# iotssb.net
KiCad netlist of a schematic drawn in EAGLE
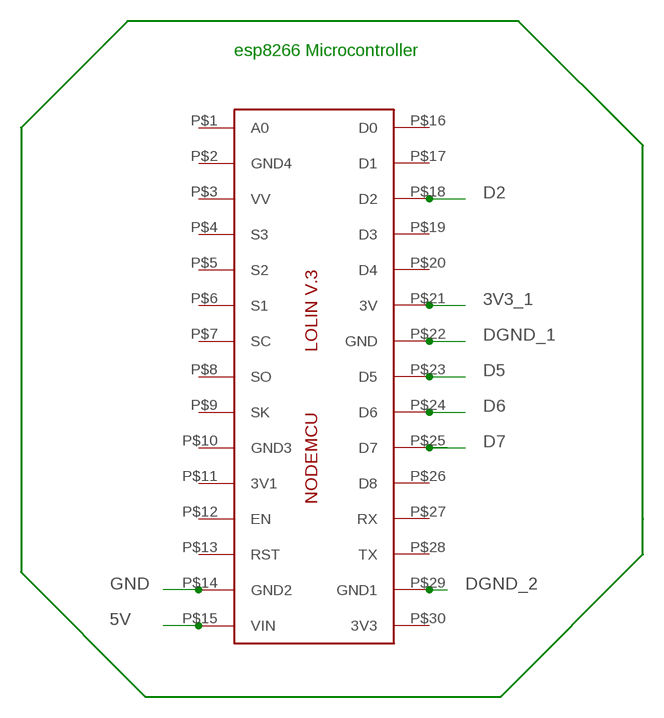
[diagram p0: schematic, sheet 1]
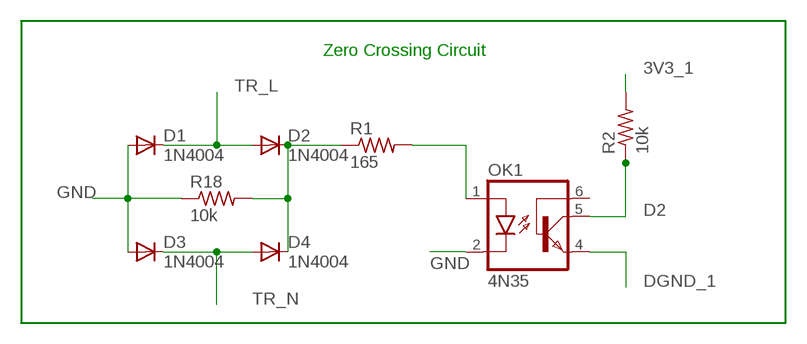
[diagram p1: schematic, sheet 2]
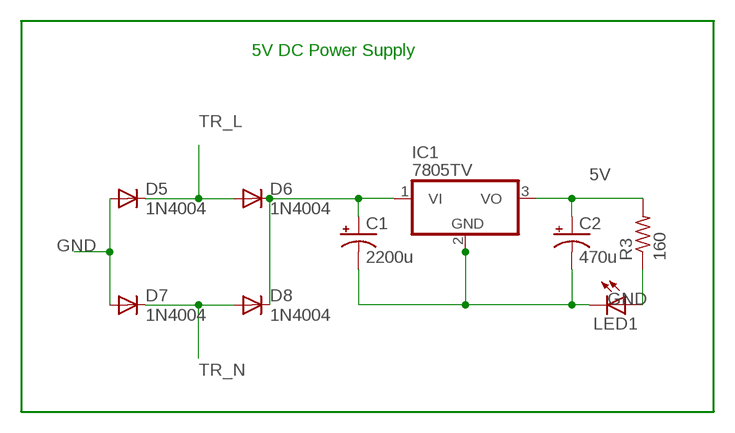
[diagram p2: schematic, sheet 3]
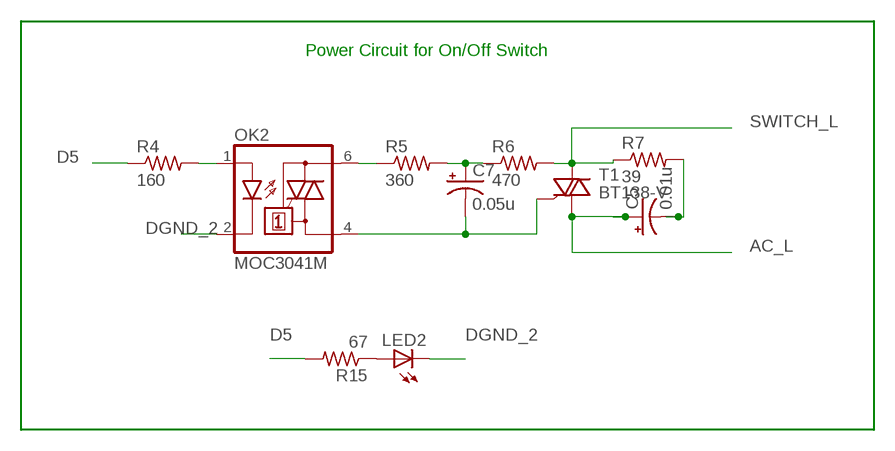
[diagram p3: schematic, sheet 4]
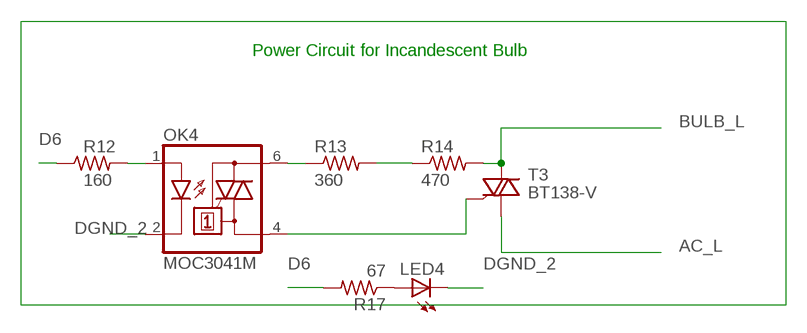
[diagram p4: schematic, sheet 5]
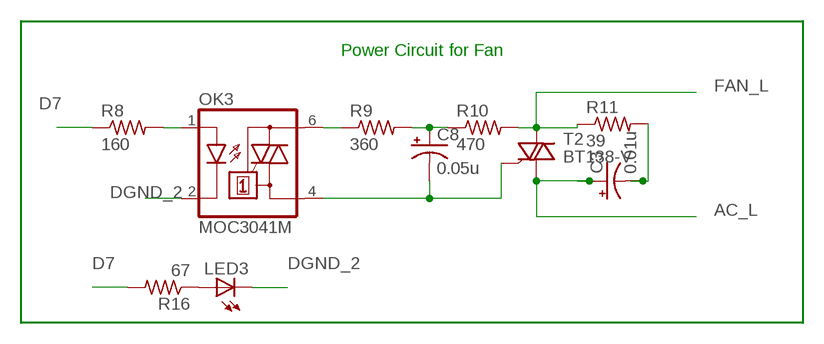
[diagram p5: schematic, sheet 6]
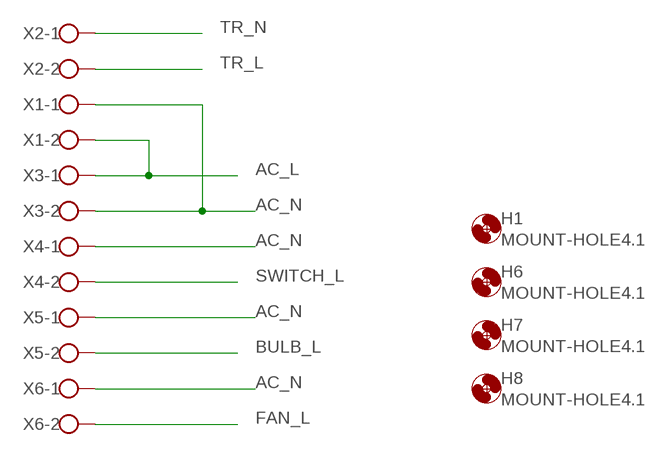
[diagram p6: schematic, sheet 7]

(export (version "E")
  (design (tool "Eeschema 10.0.6"))
  (components
    (comp (ref "C1")
      (value "2200u")
      (footprint "eagle-import:E7,5-18")
      (libsource (lib "eagle-import") (part "CPOL-USE7.5-18"))
    )
    (comp (ref "C2")
      (value "470u")
      (footprint "eagle-import:E5-13")
      (libsource (lib "eagle-import") (part "rcl_334_CPOL-USE5-13"))
    )
    (comp (ref "D5")
      (value "1N4004")
      (footprint "eagle-import:DO41-10")
      (libsource (lib "eagle-import") (part "1N4004"))
    )
    (comp (ref "D6")
      (value "1N4004")
      (footprint "eagle-import:DO41-10")
      (libsource (lib "eagle-import") (part "1N4004"))
    )
    (comp (ref "D7")
      (value "1N4004")
      (footprint "eagle-import:DO41-10")
      (libsource (lib "eagle-import") (part "1N4004"))
    )
    (comp (ref "D8")
      (value "1N4004")
      (footprint "eagle-import:DO41-10")
      (libsource (lib "eagle-import") (part "1N4004"))
    )
    (comp (ref "IC1")
      (value "7805TV")
      (footprint "eagle-import:TO220V")
      (libsource (lib "eagle-import") (part "78TV05"))
    )
    (comp (ref "LED1")
      (value "LED3MM")
      (footprint "eagle-import:LED3MM")
      (libsource (lib "eagle-import") (part "LED3MM"))
    )
    (comp (ref "R3")
      (value "160")
      (footprint "eagle-import:0207_10")
      (libsource (lib "eagle-import") (part "R-US_0207/10"))
    )
    (comp (ref "C5")
      (value "0.01u")
      (footprint "eagle-import:E5-13")
      (libsource (lib "eagle-import") (part "rcl_334_CPOL-USE5-13"))
    )
    (comp (ref "C7")
      (value "0.05u")
      (footprint "eagle-import:E5-13")
      (libsource (lib "eagle-import") (part "rcl_334_CPOL-USE5-13"))
    )
    (comp (ref "LED2")
      (value "LED3MM")
      (footprint "eagle-import:LED3MM")
      (libsource (lib "eagle-import") (part "LED3MM"))
    )
    (comp (ref "OK2")
      (value "MOC3041M")
      (footprint "eagle-import:DIL06")
      (fields (field (name "MF") "FAIRCHILD SEMICONDUCTOR"))
      (libsource (lib "eagle-import") (part "MOC3041M"))
    )
    (comp (ref "R4")
      (value "160")
      (footprint "eagle-import:0207_10")
      (libsource (lib "eagle-import") (part "R-US_0207/10"))
    )
    (comp (ref "R5")
      (value "360")
      (footprint "eagle-import:0207_15")
      (libsource (lib "eagle-import") (part "R-US_0207/15"))
    )
    (comp (ref "R6")
      (value "470")
      (footprint "eagle-import:0207_15")
      (libsource (lib "eagle-import") (part "R-US_0207/15"))
    )
    (comp (ref "R7")
      (value "39")
      (footprint "eagle-import:0207_15")
      (libsource (lib "eagle-import") (part "R-US_0207/15"))
    )
    (comp (ref "R15")
      (value "67")
      (footprint "eagle-import:0207_10")
      (libsource (lib "eagle-import") (part "R-US_0207/10"))
    )
    (comp (ref "T1")
      (value "BT138-V")
      (footprint "eagle-import:TO220BV")
      (libsource (lib "eagle-import") (part "BT138-V"))
    )
    (comp (ref "LED4")
      (value "LED3MM")
      (footprint "eagle-import:LED3MM")
      (libsource (lib "eagle-import") (part "LED3MM"))
    )
    (comp (ref "OK4")
      (value "MOC3041M")
      (footprint "eagle-import:DIL06")
      (fields (field (name "MF") "FAIRCHILD SEMICONDUCTOR"))
      (libsource (lib "eagle-import") (part "MOC3041M"))
    )
    (comp (ref "R12")
      (value "160")
      (footprint "eagle-import:0207_10")
      (libsource (lib "eagle-import") (part "R-US_0207/10"))
    )
    (comp (ref "R13")
      (value "360")
      (footprint "eagle-import:0207_15")
      (libsource (lib "eagle-import") (part "R-US_0207/15"))
    )
    (comp (ref "R14")
      (value "470")
      (footprint "eagle-import:0207_15")
      (libsource (lib "eagle-import") (part "R-US_0207/15"))
    )
    (comp (ref "R17")
      (value "67")
      (footprint "eagle-import:0207_10")
      (libsource (lib "eagle-import") (part "R-US_0207/10"))
    )
    (comp (ref "T3")
      (value "BT138-V")
      (footprint "eagle-import:TO220BV")
      (libsource (lib "eagle-import") (part "BT138-V"))
    )
    (comp (ref "C3")
      (value "0.01u")
      (footprint "eagle-import:E5-13")
      (libsource (lib "eagle-import") (part "rcl_334_CPOL-USE5-13"))
    )
    (comp (ref "C8")
      (value "0.05u")
      (footprint "eagle-import:E5-13")
      (libsource (lib "eagle-import") (part "rcl_334_CPOL-USE5-13"))
    )
    (comp (ref "LED3")
      (value "LED3MM")
      (footprint "eagle-import:LED3MM")
      (libsource (lib "eagle-import") (part "LED3MM"))
    )
    (comp (ref "OK3")
      (value "MOC3041M")
      (footprint "eagle-import:DIL06")
      (fields (field (name "MF") "FAIRCHILD SEMICONDUCTOR"))
      (libsource (lib "eagle-import") (part "MOC3041M"))
    )
    (comp (ref "R8")
      (value "160")
      (footprint "eagle-import:0207_10")
      (libsource (lib "eagle-import") (part "R-US_0207/10"))
    )
    (comp (ref "R9")
      (value "360")
      (footprint "eagle-import:0207_15")
      (libsource (lib "eagle-import") (part "R-US_0207/15"))
    )
    (comp (ref "R10")
      (value "470")
      (footprint "eagle-import:0207_15")
      (libsource (lib "eagle-import") (part "R-US_0207/15"))
    )
    (comp (ref "R11")
      (value "39")
      (footprint "eagle-import:0207_15")
      (libsource (lib "eagle-import") (part "R-US_0207/15"))
    )
    (comp (ref "R16")
      (value "67")
      (footprint "eagle-import:0207_10")
      (libsource (lib "eagle-import") (part "R-US_0207/10"))
    )
    (comp (ref "T2")
      (value "BT138-V")
      (footprint "eagle-import:TO220BV")
      (libsource (lib "eagle-import") (part "BT138-V"))
    )
    (comp (ref "IC2")
      (value "LOLINV3ESP12E")
      (footprint "eagle-import:LOL1NV0.1")
      (libsource (lib "eagle-import") (part "LOLINV3ESP12E"))
    )
    (comp (ref "D1")
      (value "1N4004")
      (footprint "eagle-import:DO41-10")
      (libsource (lib "eagle-import") (part "1N4004"))
    )
    (comp (ref "D2")
      (value "1N4004")
      (footprint "eagle-import:DO41-10")
      (libsource (lib "eagle-import") (part "1N4004"))
    )
    (comp (ref "D3")
      (value "1N4004")
      (footprint "eagle-import:DO41-10")
      (libsource (lib "eagle-import") (part "1N4004"))
    )
    (comp (ref "D4")
      (value "1N4004")
      (footprint "eagle-import:DO41-10")
      (libsource (lib "eagle-import") (part "1N4004"))
    )
    (comp (ref "OK1")
      (value "4N35")
      (footprint "eagle-import:DIL06")
      (fields (field (name "MF") "FAIRCHILD SEMICONDUCTOR"))
      (libsource (lib "eagle-import") (part "4N35"))
    )
    (comp (ref "R1")
      (value "165")
      (footprint "eagle-import:0207_10")
      (libsource (lib "eagle-import") (part "R-US_0207/10"))
    )
    (comp (ref "R2")
      (value "10k")
      (footprint "eagle-import:0207_10")
      (libsource (lib "eagle-import") (part "R-US_0207/10"))
    )
    (comp (ref "R18")
      (value "10k")
      (footprint "eagle-import:0207_10")
      (libsource (lib "eagle-import") (part "R-US_0207/10"))
    )
    (comp (ref "H1")
      (value "MOUNT-HOLE4.1")
      (footprint "eagle-import:4,1")
      (libsource (lib "eagle-import") (part "MOUNT-HOLE4.1"))
    )
    (comp (ref "H6")
      (value "MOUNT-HOLE4.1")
      (footprint "eagle-import:4,1")
      (libsource (lib "eagle-import") (part "MOUNT-HOLE4.1"))
    )
    (comp (ref "H7")
      (value "MOUNT-HOLE4.1")
      (footprint "eagle-import:4,1")
      (libsource (lib "eagle-import") (part "MOUNT-HOLE4.1"))
    )
    (comp (ref "H8")
      (value "MOUNT-HOLE4.1")
      (footprint "eagle-import:4,1")
      (libsource (lib "eagle-import") (part "MOUNT-HOLE4.1"))
    )
    (comp (ref "X1")
      (value "W237-102")
      (footprint "eagle-import:W237-102")
      (fields (field (name "MPN") "237-102"))
      (libsource (lib "eagle-import") (part "W237-102"))
    )
    (comp (ref "X2")
      (value "W237-102")
      (footprint "eagle-import:W237-102")
      (fields (field (name "MPN") "237-102"))
      (libsource (lib "eagle-import") (part "W237-102"))
    )
    (comp (ref "X3")
      (value "W237-102")
      (footprint "eagle-import:W237-102")
      (fields (field (name "MPN") "237-102"))
      (libsource (lib "eagle-import") (part "W237-102"))
    )
    (comp (ref "X4")
      (value "W237-102")
      (footprint "eagle-import:W237-102")
      (fields (field (name "MPN") "237-102"))
      (libsource (lib "eagle-import") (part "W237-102"))
    )
    (comp (ref "X5")
      (value "W237-102")
      (footprint "eagle-import:W237-102")
      (fields (field (name "MPN") "237-102"))
      (libsource (lib "eagle-import") (part "W237-102"))
    )
    (comp (ref "X6")
      (value "W237-102")
      (footprint "eagle-import:W237-102")
      (fields (field (name "MPN") "237-102"))
      (libsource (lib "eagle-import") (part "W237-102"))
    )
  )
  (nets
    (net (code "1") (name "3V3_1") (class "Default")
      (node (ref "IC2") (pin "P$21") (pinfunction "3V_P$21") (pintype "bidirectional"))
      (node (ref "R2") (pin "2") (pinfunction "2_2") (pintype "passive"))
    )
    (net (code "2") (name "5V") (class "Default")
      (node (ref "C2") (pin "+") (pinfunction "+_+") (pintype "passive"))
      (node (ref "IC1") (pin "3") (pinfunction "VO_3") (pintype "passive"))
      (node (ref "IC2") (pin "P$15") (pinfunction "VIN_P$15") (pintype "bidirectional"))
      (node (ref "R3") (pin "2") (pinfunction "2_2") (pintype "passive"))
    )
    (net (code "3") (name "AC_L") (class "Default")
      (node (ref "C3") (pin "+") (pinfunction "+_+") (pintype "passive"))
      (node (ref "C5") (pin "+") (pinfunction "+_+") (pintype "passive"))
      (node (ref "T1") (pin "T1") (pinfunction "A1_T1") (pintype "passive"))
      (node (ref "T2") (pin "T1") (pinfunction "A1_T1") (pintype "passive"))
      (node (ref "T3") (pin "T1") (pinfunction "A1_T1") (pintype "passive"))
      (node (ref "X1") (pin "2") (pinfunction "KL_2") (pintype "passive"))
      (node (ref "X3") (pin "1") (pinfunction "KL_1") (pintype "passive"))
    )
    (net (code "4") (name "AC_N") (class "Default")
      (node (ref "X1") (pin "1") (pinfunction "KL_1") (pintype "passive"))
      (node (ref "X3") (pin "2") (pinfunction "KL_2") (pintype "passive"))
      (node (ref "X4") (pin "1") (pinfunction "KL_1") (pintype "passive"))
      (node (ref "X5") (pin "1") (pinfunction "KL_1") (pintype "passive"))
      (node (ref "X6") (pin "1") (pinfunction "KL_1") (pintype "passive"))
    )
    (net (code "5") (name "BULB_L") (class "Default")
      (node (ref "R14") (pin "2") (pinfunction "2_2") (pintype "passive"))
      (node (ref "T3") (pin "T2") (pinfunction "A2_T2") (pintype "passive"))
      (node (ref "X5") (pin "2") (pinfunction "KL_2") (pintype "passive"))
    )
    (net (code "6") (name "D2") (class "Default")
      (node (ref "IC2") (pin "P$18") (pinfunction "D2_P$18") (pintype "bidirectional"))
      (node (ref "OK1") (pin "5") (pinfunction "COL_5") (pintype "passive"))
      (node (ref "R2") (pin "1") (pinfunction "1_1") (pintype "passive"))
    )
    (net (code "7") (name "D5") (class "Default")
      (node (ref "IC2") (pin "P$23") (pinfunction "D5_P$23") (pintype "bidirectional"))
      (node (ref "R15") (pin "2") (pinfunction "2_2") (pintype "passive"))
      (node (ref "R4") (pin "1") (pinfunction "1_1") (pintype "passive"))
    )
    (net (code "8") (name "D6") (class "Default")
      (node (ref "IC2") (pin "P$24") (pinfunction "D6_P$24") (pintype "bidirectional"))
      (node (ref "R12") (pin "1") (pinfunction "1_1") (pintype "passive"))
      (node (ref "R17") (pin "2") (pinfunction "2_2") (pintype "passive"))
    )
    (net (code "9") (name "D7") (class "Default")
      (node (ref "IC2") (pin "P$25") (pinfunction "D7_P$25") (pintype "bidirectional"))
      (node (ref "R16") (pin "2") (pinfunction "2_2") (pintype "passive"))
      (node (ref "R8") (pin "1") (pinfunction "1_1") (pintype "passive"))
    )
    (net (code "10") (name "DGND_1") (class "Default")
      (node (ref "IC2") (pin "P$22") (pinfunction "GND_P$22") (pintype "bidirectional"))
      (node (ref "OK1") (pin "4") (pinfunction "EMI_4") (pintype "passive"))
    )
    (net (code "11") (name "DGND_2") (class "Default")
      (node (ref "IC2") (pin "P$29") (pinfunction "GND1_P$29") (pintype "bidirectional"))
      (node (ref "LED2") (pin "K") (pinfunction "C_K") (pintype "passive"))
      (node (ref "LED3") (pin "K") (pinfunction "C_K") (pintype "passive"))
      (node (ref "LED4") (pin "K") (pinfunction "C_K") (pintype "passive"))
      (node (ref "OK2") (pin "2") (pinfunction "C_2") (pintype "passive"))
      (node (ref "OK3") (pin "2") (pinfunction "C_2") (pintype "passive"))
      (node (ref "OK4") (pin "2") (pinfunction "C_2") (pintype "passive"))
    )
    (net (code "12") (name "FAN_L") (class "Default")
      (node (ref "R10") (pin "2") (pinfunction "2_2") (pintype "passive"))
      (node (ref "R11") (pin "1") (pinfunction "1_1") (pintype "passive"))
      (node (ref "T2") (pin "T2") (pinfunction "A2_T2") (pintype "passive"))
      (node (ref "X6") (pin "2") (pinfunction "KL_2") (pintype "passive"))
    )
    (net (code "13") (name "GND") (class "Default")
      (node (ref "C1") (pin "-") (pinfunction "-_-") (pintype "passive"))
      (node (ref "C2") (pin "-") (pinfunction "-_-") (pintype "passive"))
      (node (ref "D1") (pin "A") (pinfunction "A_A") (pintype "passive"))
      (node (ref "D3") (pin "A") (pinfunction "A_A") (pintype "passive"))
      (node (ref "D5") (pin "A") (pinfunction "A_A") (pintype "passive"))
      (node (ref "D7") (pin "A") (pinfunction "A_A") (pintype "passive"))
      (node (ref "IC1") (pin "2") (pinfunction "GND_2") (pintype "passive"))
      (node (ref "IC2") (pin "P$14") (pinfunction "GND2_P$14") (pintype "bidirectional"))
      (node (ref "LED1") (pin "K") (pinfunction "C_K") (pintype "passive"))
      (node (ref "OK1") (pin "2") (pinfunction "C_2") (pintype "passive"))
      (node (ref "R18") (pin "1") (pinfunction "1_1") (pintype "passive"))
    )
    (net (code "14") (name "Net-(C3-Pad-)") (class "Default")
      (node (ref "C3") (pin "-") (pinfunction "-_-") (pintype "passive"))
      (node (ref "R11") (pin "2") (pinfunction "2_2") (pintype "passive"))
    )
    (net (code "15") (name "Net-(C5-Pad-)") (class "Default")
      (node (ref "C5") (pin "-") (pinfunction "-_-") (pintype "passive"))
      (node (ref "R7") (pin "2") (pinfunction "2_2") (pintype "passive"))
    )
    (net (code "16") (name "Net-(C7-Pad+)") (class "Default")
      (node (ref "C7") (pin "+") (pinfunction "+_+") (pintype "passive"))
      (node (ref "R5") (pin "2") (pinfunction "2_2") (pintype "passive"))
      (node (ref "R6") (pin "1") (pinfunction "1_1") (pintype "passive"))
    )
    (net (code "17") (name "Net-(C8-Pad+)") (class "Default")
      (node (ref "C8") (pin "+") (pinfunction "+_+") (pintype "passive"))
      (node (ref "R10") (pin "1") (pinfunction "1_1") (pintype "passive"))
      (node (ref "R9") (pin "2") (pinfunction "2_2") (pintype "passive"))
    )
    (net (code "18") (name "Net-(D2-PadC)") (class "Default")
      (node (ref "D2") (pin "C") (pinfunction "C_C") (pintype "passive"))
      (node (ref "D4") (pin "C") (pinfunction "C_C") (pintype "passive"))
      (node (ref "R1") (pin "1") (pinfunction "1_1") (pintype "passive"))
      (node (ref "R18") (pin "2") (pinfunction "2_2") (pintype "passive"))
    )
    (net (code "19") (name "Net-(IC1-VI)") (class "Default")
      (node (ref "C1") (pin "+") (pinfunction "+_+") (pintype "passive"))
      (node (ref "D6") (pin "C") (pinfunction "C_C") (pintype "passive"))
      (node (ref "D8") (pin "C") (pinfunction "C_C") (pintype "passive"))
      (node (ref "IC1") (pin "1") (pinfunction "VI_1") (pintype "input"))
    )
    (net (code "20") (name "Net-(LED1-PadA)") (class "Default")
      (node (ref "LED1") (pin "A") (pinfunction "A_A") (pintype "passive"))
      (node (ref "R3") (pin "1") (pinfunction "1_1") (pintype "passive"))
    )
    (net (code "21") (name "Net-(LED2-PadA)") (class "Default")
      (node (ref "LED2") (pin "A") (pinfunction "A_A") (pintype "passive"))
      (node (ref "R15") (pin "1") (pinfunction "1_1") (pintype "passive"))
    )
    (net (code "22") (name "Net-(LED3-PadA)") (class "Default")
      (node (ref "LED3") (pin "A") (pinfunction "A_A") (pintype "passive"))
      (node (ref "R16") (pin "1") (pinfunction "1_1") (pintype "passive"))
    )
    (net (code "23") (name "Net-(LED4-PadA)") (class "Default")
      (node (ref "LED4") (pin "A") (pinfunction "A_A") (pintype "passive"))
      (node (ref "R17") (pin "1") (pinfunction "1_1") (pintype "passive"))
    )
    (net (code "24") (name "Net-(OK1-A)") (class "Default")
      (node (ref "OK1") (pin "1") (pinfunction "A_1") (pintype "passive"))
      (node (ref "R1") (pin "2") (pinfunction "2_2") (pintype "passive"))
    )
    (net (code "25") (name "Net-(OK2-A)") (class "Default")
      (node (ref "OK2") (pin "1") (pinfunction "A_1") (pintype "passive"))
      (node (ref "R4") (pin "2") (pinfunction "2_2") (pintype "passive"))
    )
    (net (code "26") (name "Net-(OK2-A1)") (class "Default")
      (node (ref "C7") (pin "-") (pinfunction "-_-") (pintype "passive"))
      (node (ref "OK2") (pin "4") (pinfunction "A1_4") (pintype "passive"))
      (node (ref "T1") (pin "G") (pinfunction "G_G") (pintype "passive"))
    )
    (net (code "27") (name "Net-(OK2-A2)") (class "Default")
      (node (ref "OK2") (pin "6") (pinfunction "A2_6") (pintype "passive"))
      (node (ref "R5") (pin "1") (pinfunction "1_1") (pintype "passive"))
    )
    (net (code "28") (name "Net-(OK3-A)") (class "Default")
      (node (ref "OK3") (pin "1") (pinfunction "A_1") (pintype "passive"))
      (node (ref "R8") (pin "2") (pinfunction "2_2") (pintype "passive"))
    )
    (net (code "29") (name "Net-(OK3-A1)") (class "Default")
      (node (ref "C8") (pin "-") (pinfunction "-_-") (pintype "passive"))
      (node (ref "OK3") (pin "4") (pinfunction "A1_4") (pintype "passive"))
      (node (ref "T2") (pin "G") (pinfunction "G_G") (pintype "passive"))
    )
    (net (code "30") (name "Net-(OK3-A2)") (class "Default")
      (node (ref "OK3") (pin "6") (pinfunction "A2_6") (pintype "passive"))
      (node (ref "R9") (pin "1") (pinfunction "1_1") (pintype "passive"))
    )
    (net (code "31") (name "Net-(OK4-A)") (class "Default")
      (node (ref "OK4") (pin "1") (pinfunction "A_1") (pintype "passive"))
      (node (ref "R12") (pin "2") (pinfunction "2_2") (pintype "passive"))
    )
    (net (code "32") (name "Net-(OK4-A1)") (class "Default")
      (node (ref "OK4") (pin "4") (pinfunction "A1_4") (pintype "passive"))
      (node (ref "T3") (pin "G") (pinfunction "G_G") (pintype "passive"))
    )
    (net (code "33") (name "Net-(OK4-A2)") (class "Default")
      (node (ref "OK4") (pin "6") (pinfunction "A2_6") (pintype "passive"))
      (node (ref "R13") (pin "1") (pinfunction "1_1") (pintype "passive"))
    )
    (net (code "34") (name "Net-(R13-Pad2)") (class "Default")
      (node (ref "R13") (pin "2") (pinfunction "2_2") (pintype "passive"))
      (node (ref "R14") (pin "1") (pinfunction "1_1") (pintype "passive"))
    )
    (net (code "35") (name "SWITCH_L") (class "Default")
      (node (ref "R6") (pin "2") (pinfunction "2_2") (pintype "passive"))
      (node (ref "R7") (pin "1") (pinfunction "1_1") (pintype "passive"))
      (node (ref "T1") (pin "T2") (pinfunction "A2_T2") (pintype "passive"))
      (node (ref "X4") (pin "2") (pinfunction "KL_2") (pintype "passive"))
    )
    (net (code "36") (name "TR_L") (class "Default")
      (node (ref "D1") (pin "C") (pinfunction "C_C") (pintype "passive"))
      (node (ref "D2") (pin "A") (pinfunction "A_A") (pintype "passive"))
      (node (ref "D5") (pin "C") (pinfunction "C_C") (pintype "passive"))
      (node (ref "D6") (pin "A") (pinfunction "A_A") (pintype "passive"))
      (node (ref "X2") (pin "2") (pinfunction "KL_2") (pintype "passive"))
    )
    (net (code "37") (name "TR_N") (class "Default")
      (node (ref "D3") (pin "C") (pinfunction "C_C") (pintype "passive"))
      (node (ref "D4") (pin "A") (pinfunction "A_A") (pintype "passive"))
      (node (ref "D7") (pin "C") (pinfunction "C_C") (pintype "passive"))
      (node (ref "D8") (pin "A") (pinfunction "A_A") (pintype "passive"))
      (node (ref "X2") (pin "1") (pinfunction "KL_1") (pintype "passive"))
    )
    (net (code "38") (name "unconnected-(IC2-3V1-PadP$11)") (class "Default")
      (node (ref "IC2") (pin "P$11") (pinfunction "3V1_P$11") (pintype "bidirectional"))
    )
    (net (code "39") (name "unconnected-(IC2-3V3-PadP$30)") (class "Default")
      (node (ref "IC2") (pin "P$30") (pinfunction "3V3_P$30") (pintype "bidirectional"))
    )
    (net (code "40") (name "unconnected-(IC2-A0-PadP$1)") (class "Default")
      (node (ref "IC2") (pin "P$1") (pinfunction "A0_P$1") (pintype "bidirectional"))
    )
    (net (code "41") (name "unconnected-(IC2-D0-PadP$16)") (class "Default")
      (node (ref "IC2") (pin "P$16") (pinfunction "D0_P$16") (pintype "bidirectional"))
    )
    (net (code "42") (name "unconnected-(IC2-D1-PadP$17)") (class "Default")
      (node (ref "IC2") (pin "P$17") (pinfunction "D1_P$17") (pintype "bidirectional"))
    )
    (net (code "43") (name "unconnected-(IC2-D3-PadP$19)") (class "Default")
      (node (ref "IC2") (pin "P$19") (pinfunction "D3_P$19") (pintype "bidirectional"))
    )
    (net (code "44") (name "unconnected-(IC2-D4-PadP$20)") (class "Default")
      (node (ref "IC2") (pin "P$20") (pinfunction "D4_P$20") (pintype "bidirectional"))
    )
    (net (code "45") (name "unconnected-(IC2-D8-PadP$26)") (class "Default")
      (node (ref "IC2") (pin "P$26") (pinfunction "D8_P$26") (pintype "bidirectional"))
    )
    (net (code "46") (name "unconnected-(IC2-EN-PadP$12)") (class "Default")
      (node (ref "IC2") (pin "P$12") (pinfunction "EN_P$12") (pintype "bidirectional"))
    )
    (net (code "47") (name "unconnected-(IC2-GND3-PadP$10)") (class "Default")
      (node (ref "IC2") (pin "P$10") (pinfunction "GND3_P$10") (pintype "bidirectional"))
    )
    (net (code "48") (name "unconnected-(IC2-GND4-PadP$2)") (class "Default")
      (node (ref "IC2") (pin "P$2") (pinfunction "GND4_P$2") (pintype "bidirectional"))
    )
    (net (code "49") (name "unconnected-(IC2-RST-PadP$13)") (class "Default")
      (node (ref "IC2") (pin "P$13") (pinfunction "RST_P$13") (pintype "bidirectional"))
    )
    (net (code "50") (name "unconnected-(IC2-RX-PadP$27)") (class "Default")
      (node (ref "IC2") (pin "P$27") (pinfunction "RX_P$27") (pintype "bidirectional"))
    )
    (net (code "51") (name "unconnected-(IC2-S1-PadP$6)") (class "Default")
      (node (ref "IC2") (pin "P$6") (pinfunction "S1_P$6") (pintype "bidirectional"))
    )
    (net (code "52") (name "unconnected-(IC2-S2-PadP$5)") (class "Default")
      (node (ref "IC2") (pin "P$5") (pinfunction "S2_P$5") (pintype "bidirectional"))
    )
    (net (code "53") (name "unconnected-(IC2-S3-PadP$4)") (class "Default")
      (node (ref "IC2") (pin "P$4") (pinfunction "S3_P$4") (pintype "bidirectional"))
    )
    (net (code "54") (name "unconnected-(IC2-SC-PadP$7)") (class "Default")
      (node (ref "IC2") (pin "P$7") (pinfunction "SC_P$7") (pintype "bidirectional"))
    )
    (net (code "55") (name "unconnected-(IC2-SK-PadP$9)") (class "Default")
      (node (ref "IC2") (pin "P$9") (pinfunction "SK_P$9") (pintype "bidirectional"))
    )
    (net (code "56") (name "unconnected-(IC2-SO-PadP$8)") (class "Default")
      (node (ref "IC2") (pin "P$8") (pinfunction "SO_P$8") (pintype "bidirectional"))
    )
    (net (code "57") (name "unconnected-(IC2-TX-PadP$28)") (class "Default")
      (node (ref "IC2") (pin "P$28") (pinfunction "TX_P$28") (pintype "bidirectional"))
    )
    (net (code "58") (name "unconnected-(IC2-VV-PadP$3)") (class "Default")
      (node (ref "IC2") (pin "P$3") (pinfunction "VV_P$3") (pintype "bidirectional"))
    )
    (net (code "59") (name "unconnected-(OK1-BAS-Pad6)") (class "Default")
      (node (ref "OK1") (pin "6") (pinfunction "BAS_6") (pintype "passive"))
    )
  )
)
